# DAPlink-LPC11U35-v1_0_0.net
KiCad netlist of a schematic drawn in EAGLE
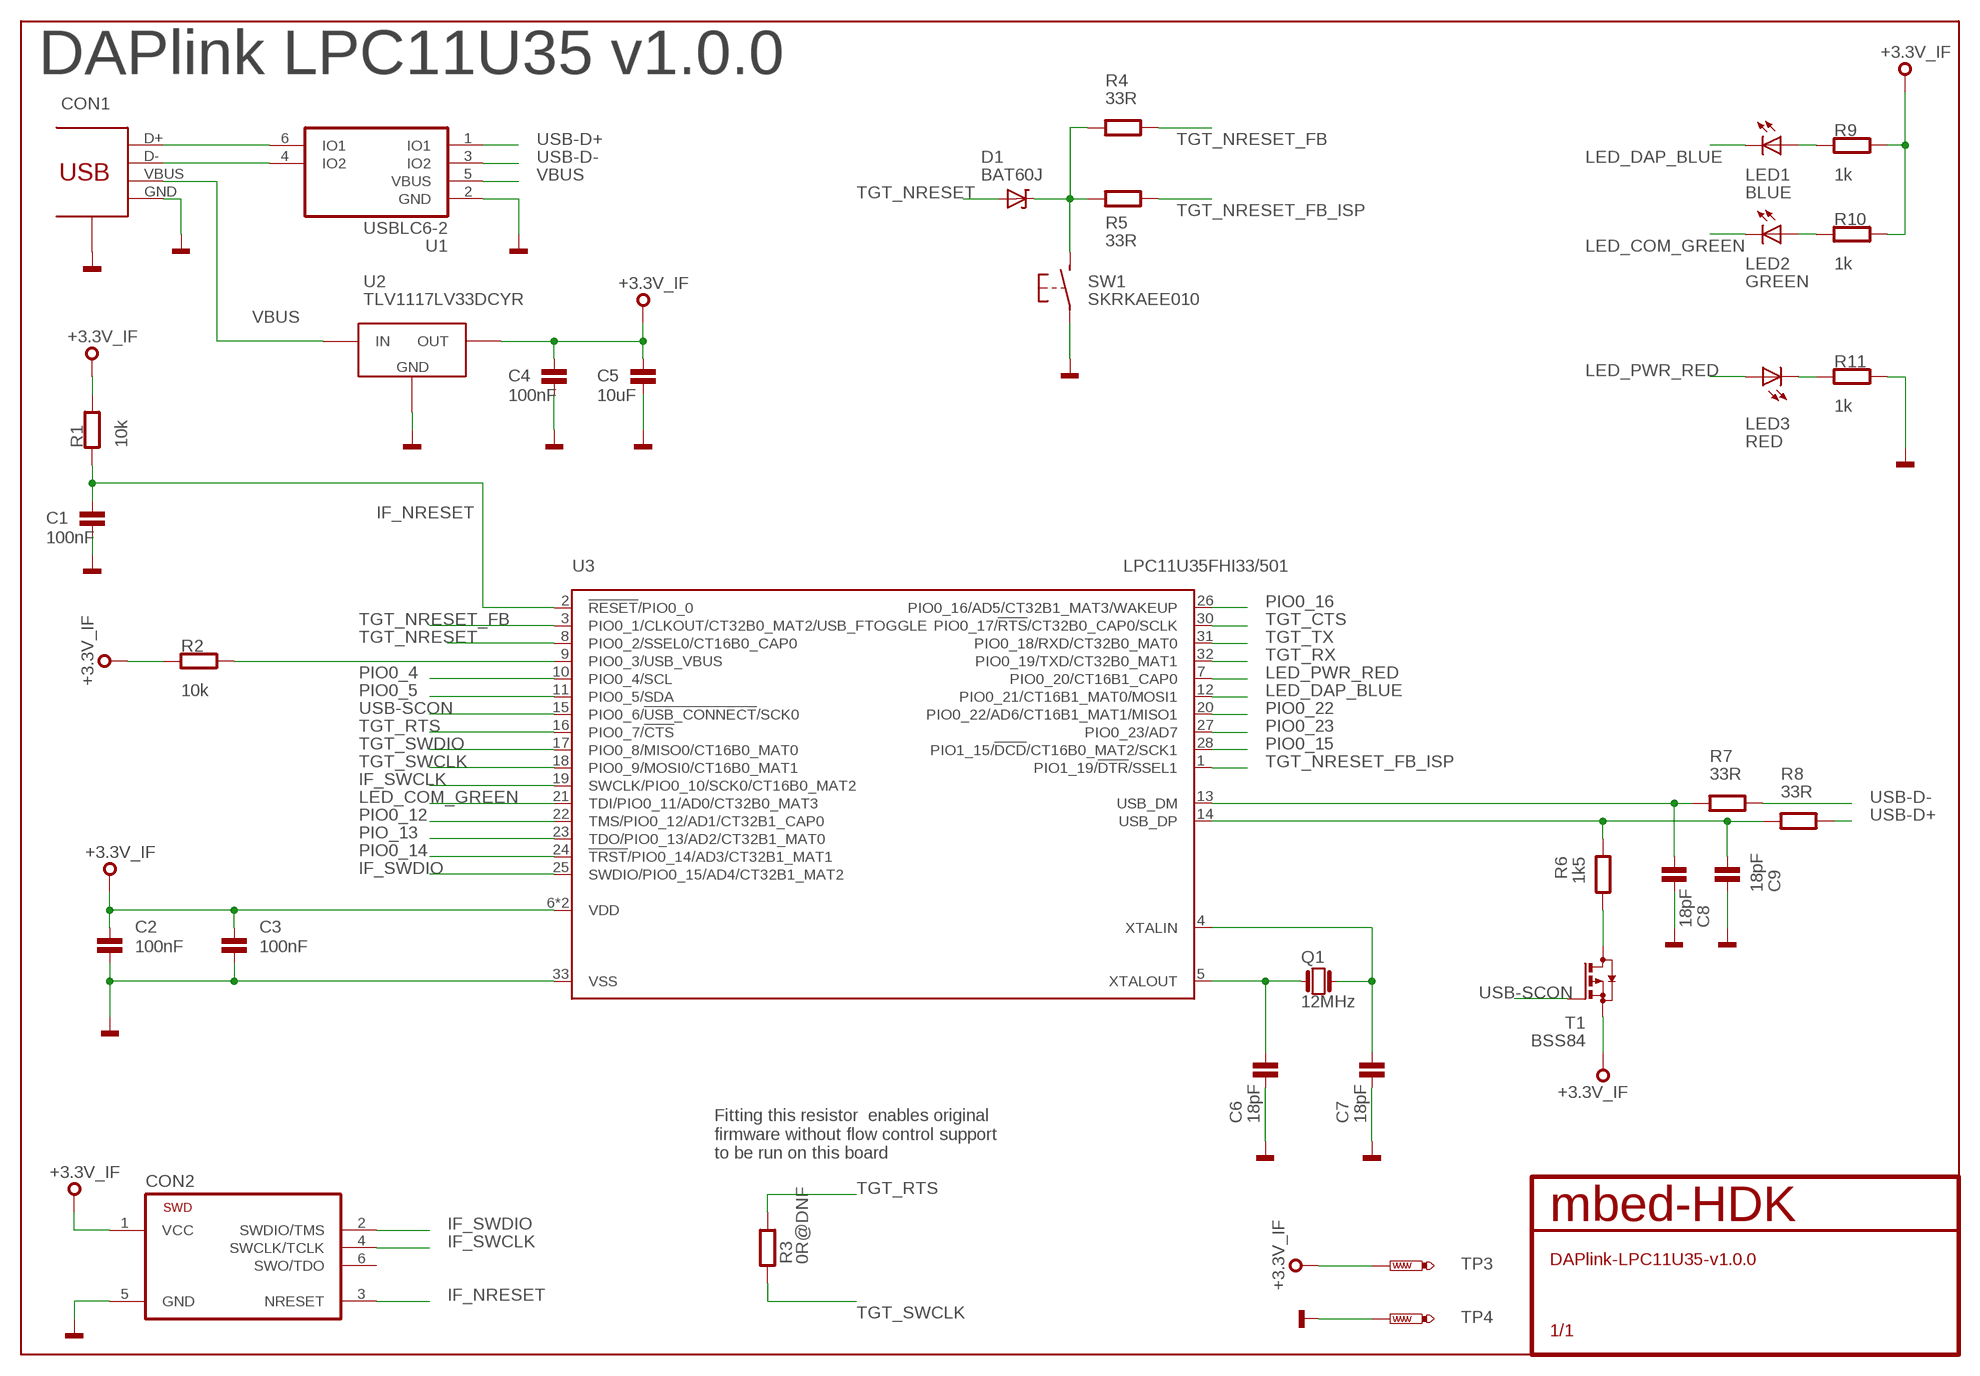
[diagram p0: schematic, sheet 1]

(export (version "E")
  (design (tool "Eeschema 10.0.6"))
  (components
    (comp (ref "C1")
      (value "100nF")
      (footprint "eagle-import:0603")
      (libsource (lib "eagle-import") (part "C0603"))
    )
    (comp (ref "C2")
      (value "100nF")
      (footprint "eagle-import:0603")
      (libsource (lib "eagle-import") (part "C0603"))
    )
    (comp (ref "C3")
      (value "100nF")
      (footprint "eagle-import:0603")
      (libsource (lib "eagle-import") (part "C0603"))
    )
    (comp (ref "C4")
      (value "100nF")
      (footprint "eagle-import:0603")
      (libsource (lib "eagle-import") (part "C0603"))
    )
    (comp (ref "C5")
      (value "10uF")
      (footprint "eagle-import:0603")
      (libsource (lib "eagle-import") (part "C0603"))
    )
    (comp (ref "C6")
      (value "18pF")
      (footprint "eagle-import:0603")
      (libsource (lib "eagle-import") (part "C0603"))
    )
    (comp (ref "C7")
      (value "18pF")
      (footprint "eagle-import:0603")
      (libsource (lib "eagle-import") (part "C0603"))
    )
    (comp (ref "C8")
      (value "18pF")
      (footprint "eagle-import:0603")
      (libsource (lib "eagle-import") (part "C0603"))
    )
    (comp (ref "C9")
      (value "18pF")
      (footprint "eagle-import:0603")
      (libsource (lib "eagle-import") (part "C0603"))
    )
    (comp (ref "CON1")
      (value "47346-0001")
      (footprint "eagle-import:USB-MICRO-B-H")
      (fields (field (name "MF") "MOLEX"))
      (libsource (lib "eagle-import") (part "47346-0001"))
    )
    (comp (ref "CON2")
      (value "TC2030-CTX-NL")
      (footprint "eagle-import:TC2030-CTX-NL")
      (libsource (lib "eagle-import") (part "TC2030-CTX-NL"))
    )
    (comp (ref "D1")
      (value "BAT60J")
      (footprint "eagle-import:SOD323")
      (fields (field (name "MF") "STMicroelectronics"))
      (libsource (lib "eagle-import") (part "BAT60J"))
    )
    (comp (ref "LED1")
      (value "BLUE")
      (footprint "eagle-import:CHIPLED_0603")
      (libsource (lib "eagle-import") (part "LED0603"))
    )
    (comp (ref "LED2")
      (value "GREEN")
      (footprint "eagle-import:CHIPLED_0603")
      (libsource (lib "eagle-import") (part "LED0603"))
    )
    (comp (ref "LED3")
      (value "RED")
      (footprint "eagle-import:CHIPLED_0603")
      (libsource (lib "eagle-import") (part "LED0603"))
    )
    (comp (ref "Q1")
      (value "12MHz")
      (footprint "eagle-import:3.2X.2.5")
      (libsource (lib "eagle-import") (part "Q_3.2X2.5"))
    )
    (comp (ref "R1")
      (value "10k")
      (footprint "eagle-import:0603")
      (libsource (lib "eagle-import") (part "R0603"))
    )
    (comp (ref "R2")
      (value "10k")
      (footprint "eagle-import:0603")
      (libsource (lib "eagle-import") (part "R0603"))
    )
    (comp (ref "R3")
      (value "0R@DNF")
      (footprint "eagle-import:0603")
      (libsource (lib "eagle-import") (part "R0603"))
    )
    (comp (ref "R4")
      (value "33R")
      (footprint "eagle-import:0603")
      (libsource (lib "eagle-import") (part "R0603"))
    )
    (comp (ref "R5")
      (value "33R")
      (footprint "eagle-import:0603")
      (libsource (lib "eagle-import") (part "R0603"))
    )
    (comp (ref "R6")
      (value "1k5")
      (footprint "eagle-import:0603")
      (libsource (lib "eagle-import") (part "R0603"))
    )
    (comp (ref "R7")
      (value "33R")
      (footprint "eagle-import:0603")
      (libsource (lib "eagle-import") (part "R0603"))
    )
    (comp (ref "R8")
      (value "33R")
      (footprint "eagle-import:0603")
      (libsource (lib "eagle-import") (part "R0603"))
    )
    (comp (ref "R9")
      (value "1k")
      (footprint "eagle-import:0603")
      (libsource (lib "eagle-import") (part "R0603"))
    )
    (comp (ref "R10")
      (value "1k")
      (footprint "eagle-import:0603")
      (libsource (lib "eagle-import") (part "R0603"))
    )
    (comp (ref "R11")
      (value "1k")
      (footprint "eagle-import:0603")
      (libsource (lib "eagle-import") (part "R0603"))
    )
    (comp (ref "SW1")
      (value "SKRKAEE010")
      (footprint "eagle-import:SKRKAEE010")
      (fields (field (name "MF") "ALPS"))
      (libsource (lib "eagle-import") (part "SKRKAEE010"))
    )
    (comp (ref "T1")
      (value "BSS84")
      (footprint "eagle-import:SOT23-3")
      (fields (field (name "MF") "Fairchild Semiconductor"))
      (libsource (lib "eagle-import") (part "BSS84"))
    )
    (comp (ref "TP3")
      (value "PTR1TP07R")
      (footprint "eagle-import:TP07R")
      (libsource (lib "eagle-import") (part "PTR1TP07R"))
    )
    (comp (ref "TP4")
      (value "PTR1TP07R")
      (footprint "eagle-import:TP07R")
      (libsource (lib "eagle-import") (part "PTR1TP07R"))
    )
    (comp (ref "U1")
      (value "USBLC6-2SC6")
      (footprint "eagle-import:SOT23-6L")
      (libsource (lib "eagle-import") (part "USBLC6-2SC6"))
    )
    (comp (ref "U2")
      (value "TLV1117LV33DCYR")
      (footprint "eagle-import:SOT223")
      (fields (field (name "MF") "Texas Instruments"))
      (libsource (lib "eagle-import") (part "TLV1117LV33DCYR"))
    )
    (comp (ref "U3")
      (value "LPC11U35FHI33/501")
      (footprint "eagle-import:SOT617-3")
      (fields (field (name "MF") "NXP"))
      (libsource (lib "eagle-import") (part "LPC11U35FHI33/501"))
    )
  )
  (nets
    (net (code "1") (name "+3.3V_IF") (class "Default")
      (node (ref "C2") (pin "1") (pinfunction "P$1_1") (pintype "passive"))
      (node (ref "C3") (pin "1") (pinfunction "P$1_1") (pintype "passive"))
      (node (ref "C4") (pin "1") (pinfunction "P$1_1") (pintype "passive"))
      (node (ref "C5") (pin "1") (pinfunction "P$1_1") (pintype "passive"))
      (node (ref "CON2") (pin "1") (pinfunction "VCC_1") (pintype "passive"))
      (node (ref "R1") (pin "2") (pinfunction "P$2_2") (pintype "passive"))
      (node (ref "R10") (pin "2") (pinfunction "P$2_2") (pintype "passive"))
      (node (ref "R2") (pin "1") (pinfunction "P$1_1") (pintype "passive"))
      (node (ref "R9") (pin "2") (pinfunction "P$2_2") (pintype "passive"))
      (node (ref "T1") (pin "2") (pinfunction "S_2") (pintype "passive"))
      (node (ref "TP3") (pin "TP") (pinfunction "TP_TP") (pintype "input"))
      (node (ref "U2") (pin "2") (pinfunction "OUT_2") (pintype "bidirectional"))
      (node (ref "U2") (pin "4") (pinfunction "OUT_4") (pintype "bidirectional"))
      (node (ref "U3") (pin "29") (pinfunction "VDD_29") (pintype "passive"))
      (node (ref "U3") (pin "6") (pinfunction "VDD_6") (pintype "passive"))
    )
    (net (code "2") (name "/IF_NRESET") (class "Default")
      (node (ref "C1") (pin "1") (pinfunction "P$1_1") (pintype "passive"))
      (node (ref "CON2") (pin "3") (pinfunction "NRESET_3") (pintype "passive"))
      (node (ref "R1") (pin "1") (pinfunction "P$1_1") (pintype "passive"))
      (node (ref "U3") (pin "2") (pinfunction "~{RESET}/PIO0_0_2") (pintype "bidirectional"))
    )
    (net (code "3") (name "/IF_SWCLK") (class "Default")
      (node (ref "CON2") (pin "4") (pinfunction "SWCLK/TCLK_4") (pintype "passive"))
      (node (ref "U3") (pin "19") (pinfunction "SWCLK/PIO0_10/SCK0/CT16B0_MAT2_19") (pintype "bidirectional"))
    )
    (net (code "4") (name "/IF_SWDIO") (class "Default")
      (node (ref "CON2") (pin "2") (pinfunction "SWDIO/TMS_2") (pintype "passive"))
      (node (ref "U3") (pin "25") (pinfunction "SWDIO/PIO0_15/AD4/CT32B1_MAT2_25") (pintype "bidirectional"))
    )
    (net (code "5") (name "/LED_COM_GREEN") (class "Default")
      (node (ref "LED2") (pin "C") (pinfunction "C_C") (pintype "passive"))
      (node (ref "U3") (pin "21") (pinfunction "TDI/PIO0_11/AD0/CT32B0_MAT3_21") (pintype "bidirectional"))
    )
    (net (code "6") (name "/LED_DAP_BLUE") (class "Default")
      (node (ref "LED1") (pin "C") (pinfunction "C_C") (pintype "passive"))
      (node (ref "U3") (pin "12") (pinfunction "PIO0_21/CT16B1_MAT0/MOSI1_12") (pintype "bidirectional"))
    )
    (net (code "7") (name "/LED_PWR_RED") (class "Default")
      (node (ref "LED3") (pin "A") (pinfunction "A_A") (pintype "passive"))
      (node (ref "U3") (pin "7") (pinfunction "PIO0_20/CT16B1_CAP0_7") (pintype "bidirectional"))
    )
    (net (code "8") (name "/PIO0_4") (class "Default")
      (node (ref "U3") (pin "10") (pinfunction "PIO0_4/SCL_10") (pintype "bidirectional"))
    )
    (net (code "9") (name "/PIO0_5") (class "Default")
      (node (ref "U3") (pin "11") (pinfunction "PIO0_5/SDA_11") (pintype "bidirectional"))
    )
    (net (code "10") (name "/PIO0_12") (class "Default")
      (node (ref "U3") (pin "22") (pinfunction "TMS/PIO0_12/AD1/CT32B1_CAP0_22") (pintype "bidirectional"))
    )
    (net (code "11") (name "/PIO0_14") (class "Default")
      (node (ref "U3") (pin "24") (pinfunction "~{TRST}/PIO0_14/AD3/CT32B1_MAT1_24") (pintype "bidirectional"))
    )
    (net (code "12") (name "/PIO0_15") (class "Default")
      (node (ref "U3") (pin "28") (pinfunction "PIO1_15/~{DCD}/CT16B0_MAT2/SCK1_28") (pintype "bidirectional"))
    )
    (net (code "13") (name "/PIO0_16") (class "Default")
      (node (ref "U3") (pin "26") (pinfunction "PIO0_16/AD5/CT32B1_MAT3/WAKEUP_26") (pintype "bidirectional"))
    )
    (net (code "14") (name "/PIO0_22") (class "Default")
      (node (ref "U3") (pin "20") (pinfunction "PIO0_22/AD6/CT16B1_MAT1/MISO1_20") (pintype "bidirectional"))
    )
    (net (code "15") (name "/PIO0_23") (class "Default")
      (node (ref "U3") (pin "27") (pinfunction "PIO0_23/AD7_27") (pintype "bidirectional"))
    )
    (net (code "16") (name "/PIO_13") (class "Default")
      (node (ref "U3") (pin "23") (pinfunction "TDO/PIO0_13/AD2/CT32B1_MAT0_23") (pintype "bidirectional"))
    )
    (net (code "17") (name "/TGT_CTS") (class "Default")
      (node (ref "U3") (pin "30") (pinfunction "PIO0_17/~{RTS}/CT32B0_CAP0/SCLK_30") (pintype "bidirectional"))
    )
    (net (code "18") (name "/TGT_NRESET") (class "Default")
      (node (ref "D1") (pin "A") (pinfunction "A_A") (pintype "passive"))
      (node (ref "U3") (pin "8") (pinfunction "PIO0_2/SSEL0/CT16B0_CAP0_8") (pintype "bidirectional"))
    )
    (net (code "19") (name "/TGT_NRESET_FB") (class "Default")
      (node (ref "R4") (pin "1") (pinfunction "P$1_1") (pintype "passive"))
      (node (ref "U3") (pin "3") (pinfunction "PIO0_1/CLKOUT/CT32B0_MAT2/USB_FTOGGLE_3") (pintype "bidirectional"))
    )
    (net (code "20") (name "/TGT_NRESET_FB_ISP") (class "Default")
      (node (ref "R5") (pin "1") (pinfunction "P$1_1") (pintype "passive"))
      (node (ref "U3") (pin "1") (pinfunction "PIO1_19/~{DTR}/SSEL1_1") (pintype "bidirectional"))
    )
    (net (code "21") (name "/TGT_RTS") (class "Default")
      (node (ref "R3") (pin "2") (pinfunction "P$2_2") (pintype "passive"))
      (node (ref "U3") (pin "16") (pinfunction "PIO0_7/~{CTS}_16") (pintype "bidirectional"))
    )
    (net (code "22") (name "/TGT_RX") (class "Default")
      (node (ref "U3") (pin "32") (pinfunction "PIO0_19/TXD/CT32B0_MAT1_32") (pintype "bidirectional"))
    )
    (net (code "23") (name "/TGT_SWCLK") (class "Default")
      (node (ref "R3") (pin "1") (pinfunction "P$1_1") (pintype "passive"))
      (node (ref "U3") (pin "18") (pinfunction "PIO0_9/MOSI0/CT16B0_MAT1_18") (pintype "bidirectional"))
    )
    (net (code "24") (name "/TGT_SWDIO") (class "Default")
      (node (ref "U3") (pin "17") (pinfunction "PIO0_8/MISO0/CT16B0_MAT0_17") (pintype "bidirectional"))
    )
    (net (code "25") (name "/TGT_TX") (class "Default")
      (node (ref "U3") (pin "31") (pinfunction "PIO0_18/RXD/CT32B0_MAT0_31") (pintype "bidirectional"))
    )
    (net (code "26") (name "/USB-D+") (class "Default")
      (node (ref "R8") (pin "1") (pinfunction "P$1_1") (pintype "passive"))
      (node (ref "U1") (pin "1") (pinfunction "IO1_1") (pintype "bidirectional"))
    )
    (net (code "27") (name "/USB-D-") (class "Default")
      (node (ref "R7") (pin "1") (pinfunction "P$1_1") (pintype "passive"))
      (node (ref "U1") (pin "3") (pinfunction "IO2_3") (pintype "bidirectional"))
    )
    (net (code "28") (name "/USB-SCON") (class "Default")
      (node (ref "T1") (pin "1") (pinfunction "G_1") (pintype "passive"))
      (node (ref "U3") (pin "15") (pinfunction "PIO0_6/~{USB_CONNECT}/SCK0_15") (pintype "bidirectional"))
    )
    (net (code "29") (name "/VBUS") (class "Default")
      (node (ref "CON1") (pin "VBUS") (pinfunction "VBUS_VBUS") (pintype "bidirectional"))
      (node (ref "U1") (pin "5") (pinfunction "VBUS_5") (pintype "bidirectional"))
      (node (ref "U2") (pin "3") (pinfunction "IN_3") (pintype "bidirectional"))
    )
    (net (code "30") (name "GND") (class "Default")
      (node (ref "C1") (pin "2") (pinfunction "P$2_2") (pintype "passive"))
      (node (ref "C2") (pin "2") (pinfunction "P$2_2") (pintype "passive"))
      (node (ref "C3") (pin "2") (pinfunction "P$2_2") (pintype "passive"))
      (node (ref "C4") (pin "2") (pinfunction "P$2_2") (pintype "passive"))
      (node (ref "C5") (pin "2") (pinfunction "P$2_2") (pintype "passive"))
      (node (ref "C6") (pin "2") (pinfunction "P$2_2") (pintype "passive"))
      (node (ref "C7") (pin "2") (pinfunction "P$2_2") (pintype "passive"))
      (node (ref "C8") (pin "2") (pinfunction "P$2_2") (pintype "passive"))
      (node (ref "C9") (pin "2") (pinfunction "P$2_2") (pintype "passive"))
      (node (ref "CON1") (pin "GND") (pinfunction "GND_GND") (pintype "bidirectional"))
      (node (ref "CON1") (pin "GND1") (pinfunction "SHEILD_GND1") (pintype "bidirectional"))
      (node (ref "CON1") (pin "GND2") (pinfunction "SHEILD_GND2") (pintype "bidirectional"))
      (node (ref "CON1") (pin "GND3") (pinfunction "SHEILD_GND3") (pintype "bidirectional"))
      (node (ref "CON1") (pin "GND4") (pinfunction "SHEILD_GND4") (pintype "bidirectional"))
      (node (ref "CON2") (pin "5") (pinfunction "GND_5") (pintype "passive"))
      (node (ref "R11") (pin "2") (pinfunction "P$2_2") (pintype "passive"))
      (node (ref "SW1") (pin "P$1") (pinfunction "P_P$1") (pintype "passive"))
      (node (ref "TP4") (pin "TP") (pinfunction "TP_TP") (pintype "input"))
      (node (ref "U1") (pin "2") (pinfunction "GND_2") (pintype "bidirectional"))
      (node (ref "U2") (pin "1") (pinfunction "GND_1") (pintype "bidirectional"))
      (node (ref "U3") (pin "33") (pinfunction "VSS_33") (pintype "passive"))
    )
    (net (code "31") (name "Net-(C6-P$1)") (class "Default")
      (node (ref "C6") (pin "1") (pinfunction "P$1_1") (pintype "passive"))
      (node (ref "Q1") (pin "P$1") (pinfunction "1_P$1") (pintype "passive"))
      (node (ref "U3") (pin "5") (pinfunction "XTALOUT_5") (pintype "output"))
    )
    (net (code "32") (name "Net-(C7-P$1)") (class "Default")
      (node (ref "C7") (pin "1") (pinfunction "P$1_1") (pintype "passive"))
      (node (ref "Q1") (pin "P$3") (pinfunction "2_P$3") (pintype "passive"))
      (node (ref "U3") (pin "4") (pinfunction "XTALIN_4") (pintype "input"))
    )
    (net (code "33") (name "Net-(C8-P$1)") (class "Default")
      (node (ref "C8") (pin "1") (pinfunction "P$1_1") (pintype "passive"))
      (node (ref "R7") (pin "2") (pinfunction "P$2_2") (pintype "passive"))
      (node (ref "U3") (pin "13") (pinfunction "USB_DM_13") (pintype "bidirectional"))
    )
    (net (code "34") (name "Net-(C9-P$1)") (class "Default")
      (node (ref "C9") (pin "1") (pinfunction "P$1_1") (pintype "passive"))
      (node (ref "R6") (pin "2") (pinfunction "P$2_2") (pintype "passive"))
      (node (ref "R8") (pin "2") (pinfunction "P$2_2") (pintype "passive"))
      (node (ref "U3") (pin "14") (pinfunction "USB_DP_14") (pintype "bidirectional"))
    )
    (net (code "35") (name "Net-(CON1-PadD+)") (class "Default")
      (node (ref "CON1") (pin "D+") (pinfunction "D+_D+") (pintype "bidirectional"))
      (node (ref "U1") (pin "6") (pinfunction "IO1_6") (pintype "bidirectional"))
    )
    (net (code "36") (name "Net-(CON1-PadD-)") (class "Default")
      (node (ref "CON1") (pin "D-") (pinfunction "D-_D-") (pintype "bidirectional"))
      (node (ref "U1") (pin "4") (pinfunction "IO2_4") (pintype "bidirectional"))
    )
    (net (code "37") (name "Net-(R2-P$2)") (class "Default")
      (node (ref "R2") (pin "2") (pinfunction "P$2_2") (pintype "passive"))
      (node (ref "U3") (pin "9") (pinfunction "PIO0_3/USB_VBUS_9") (pintype "bidirectional"))
    )
    (net (code "38") (name "Net-(R4-P$2)") (class "Default")
      (node (ref "D1") (pin "K") (pinfunction "K_K") (pintype "passive"))
      (node (ref "R4") (pin "2") (pinfunction "P$2_2") (pintype "passive"))
      (node (ref "R5") (pin "2") (pinfunction "P$2_2") (pintype "passive"))
      (node (ref "SW1") (pin "P$2") (pinfunction "S_P$2") (pintype "passive"))
    )
    (net (code "39") (name "Net-(R6-P$1)") (class "Default")
      (node (ref "R6") (pin "1") (pinfunction "P$1_1") (pintype "passive"))
      (node (ref "T1") (pin "3") (pinfunction "D_3") (pintype "passive"))
    )
    (net (code "40") (name "Net-(R9-P$1)") (class "Default")
      (node (ref "LED1") (pin "A") (pinfunction "A_A") (pintype "passive"))
      (node (ref "R9") (pin "1") (pinfunction "P$1_1") (pintype "passive"))
    )
    (net (code "41") (name "Net-(R10-P$1)") (class "Default")
      (node (ref "LED2") (pin "A") (pinfunction "A_A") (pintype "passive"))
      (node (ref "R10") (pin "1") (pinfunction "P$1_1") (pintype "passive"))
    )
    (net (code "42") (name "Net-(R11-P$1)") (class "Default")
      (node (ref "LED3") (pin "C") (pinfunction "C_C") (pintype "passive"))
      (node (ref "R11") (pin "1") (pinfunction "P$1_1") (pintype "passive"))
    )
    (net (code "43") (name "unconnected-(CON2-SWO{slash}TDO-Pad6)") (class "Default")
      (node (ref "CON2") (pin "6") (pinfunction "SWO/TDO_6") (pintype "passive"))
    )
  )
)
